# tester_tlumivek.net
KiCad netlist of a schematic drawn in EAGLE
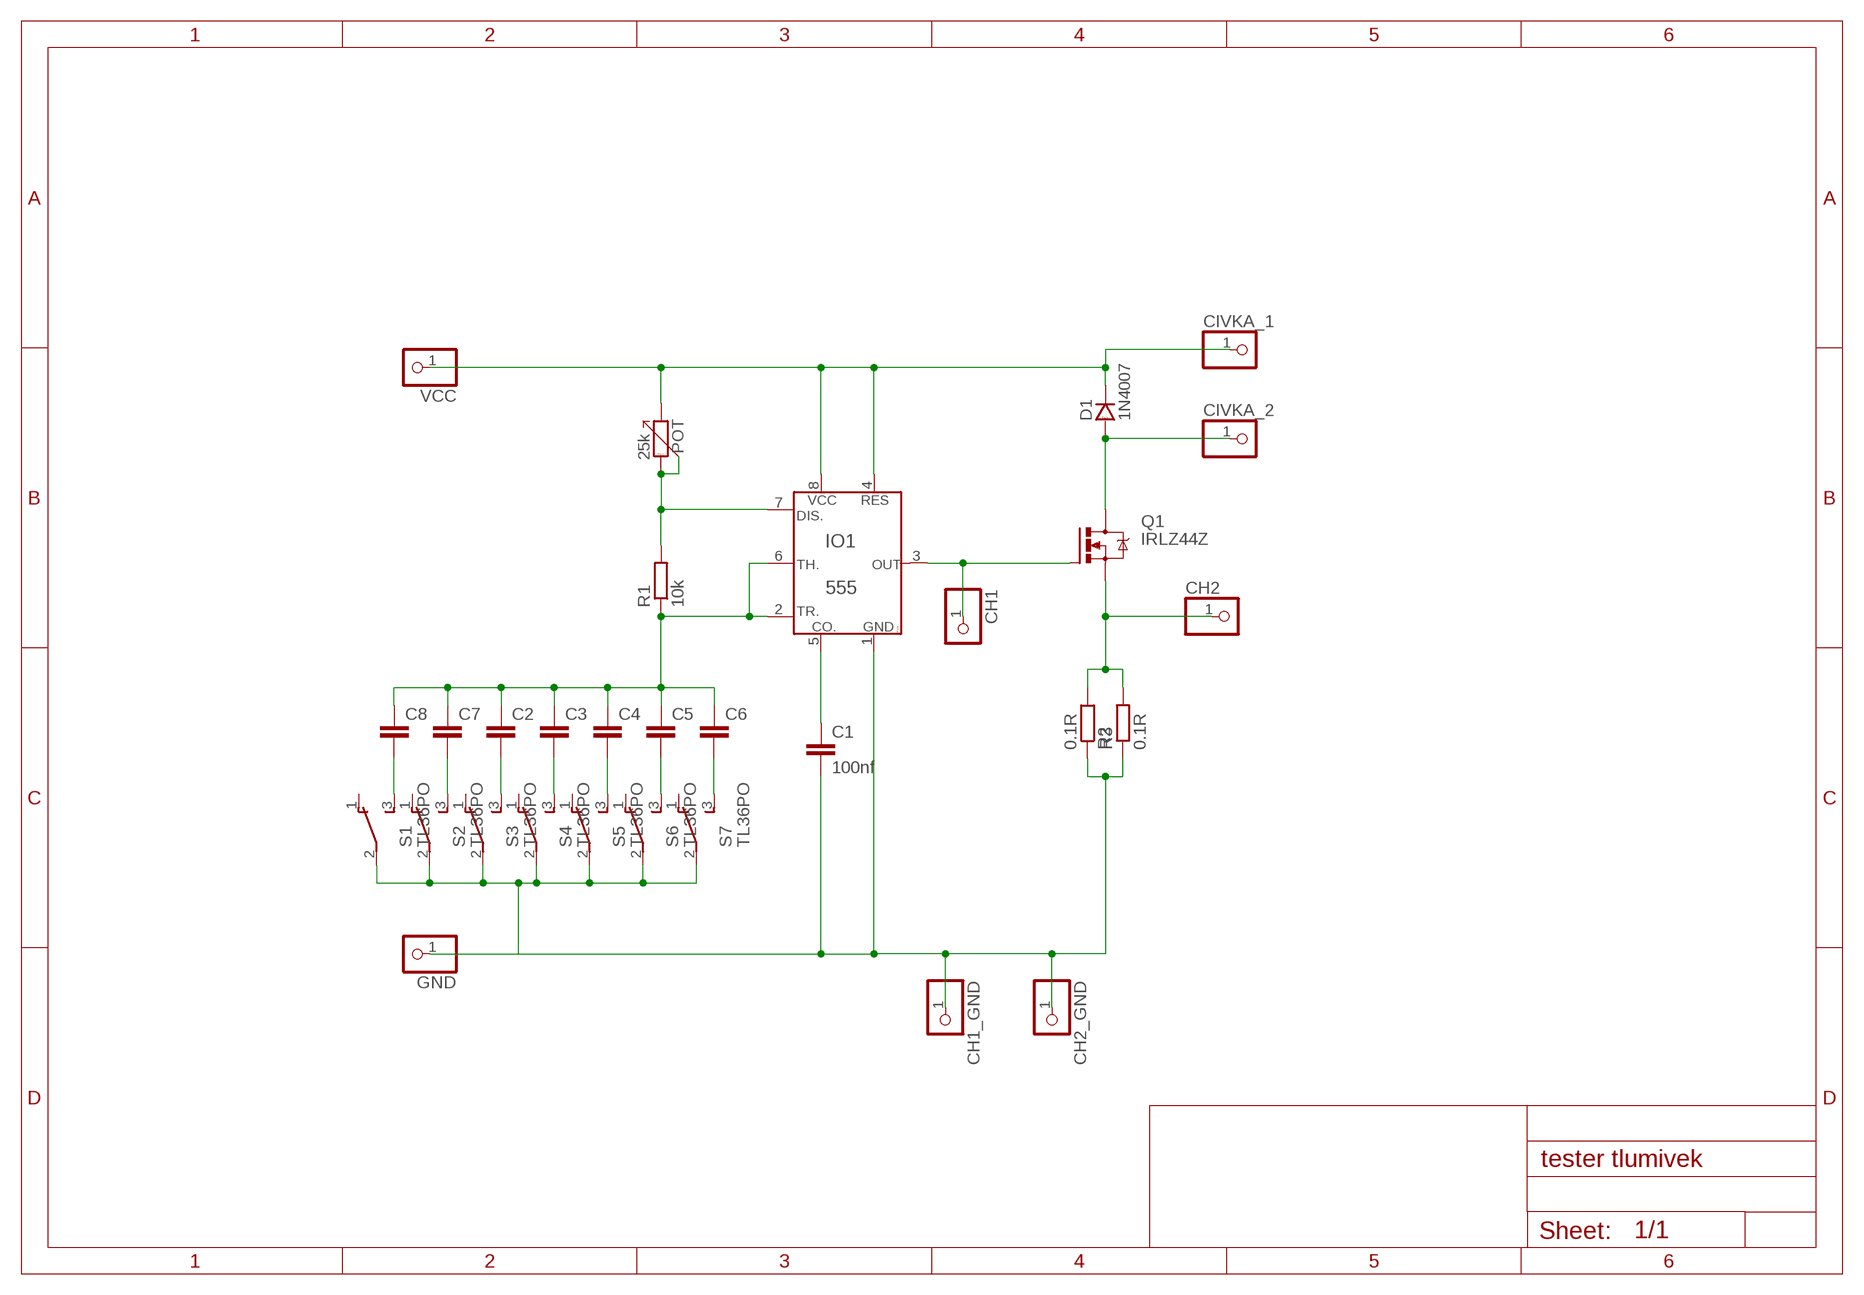
[diagram p0: schematic, sheet 1]

(export (version "E")
  (design (tool "Eeschema 10.0.6"))
  (components
    (comp (ref "C1")
      (value "100nf")
      (footprint "eagle-import:C075-042X103")
      (libsource (lib "eagle-import") (part "C-EU075-042X103"))
    )
    (comp (ref "C2")
      (value "C-EU075-042X103")
      (footprint "eagle-import:C075-042X103")
      (libsource (lib "eagle-import") (part "C-EU075-042X103"))
    )
    (comp (ref "C3")
      (value "C-EU075-042X103")
      (footprint "eagle-import:C075-042X103")
      (libsource (lib "eagle-import") (part "C-EU075-042X103"))
    )
    (comp (ref "C4")
      (value "C-EU075-042X103")
      (footprint "eagle-import:C075-042X103")
      (libsource (lib "eagle-import") (part "C-EU075-042X103"))
    )
    (comp (ref "C5")
      (value "C-EU075-042X103")
      (footprint "eagle-import:C075-042X103")
      (libsource (lib "eagle-import") (part "C-EU075-042X103"))
    )
    (comp (ref "C6")
      (value "C-EU075-042X103")
      (footprint "eagle-import:C075-042X103")
      (libsource (lib "eagle-import") (part "C-EU075-042X103"))
    )
    (comp (ref "C7")
      (value "C-EU075-042X103")
      (footprint "eagle-import:C075-042X103")
      (libsource (lib "eagle-import") (part "C-EU075-042X103"))
    )
    (comp (ref "C8")
      (value "C-EU075-042X103")
      (footprint "eagle-import:C075-042X103")
      (libsource (lib "eagle-import") (part "C-EU075-042X103"))
    )
    (comp (ref "CH1")
      (value "PINHD-1X1")
      (footprint "eagle-import:1X01")
      (libsource (lib "eagle-import") (part "PINHD-1X1"))
    )
    (comp (ref "CH1_GND")
      (value "PINHD-1X1")
      (footprint "eagle-import:1X01")
      (libsource (lib "eagle-import") (part "PINHD-1X1"))
    )
    (comp (ref "CH2")
      (value "PINHD-1X1")
      (footprint "eagle-import:1X01")
      (libsource (lib "eagle-import") (part "PINHD-1X1"))
    )
    (comp (ref "CH2_GND")
      (value "PINHD-1X1")
      (footprint "eagle-import:1X01")
      (libsource (lib "eagle-import") (part "PINHD-1X1"))
    )
    (comp (ref "CIVKA_1")
      (value "PINHD-1X1")
      (footprint "eagle-import:1X01")
      (libsource (lib "eagle-import") (part "PINHD-1X1"))
    )
    (comp (ref "CIVKA_2")
      (value "PINHD-1X1")
      (footprint "eagle-import:1X01")
      (libsource (lib "eagle-import") (part "PINHD-1X1"))
    )
    (comp (ref "D1")
      (value "1N4007")
      (footprint "eagle-import:DO41")
      (libsource (lib "eagle-import") (part "1N4007"))
    )
    (comp (ref "GND")
      (value "PINHD-1X1")
      (footprint "eagle-import:1X01")
      (libsource (lib "eagle-import") (part "PINHD-1X1"))
    )
    (comp (ref "IO1")
      (value "555")
      (footprint "eagle-import:DIL8")
      (libsource (lib "eagle-import") (part "555"))
    )
    (comp (ref "POT")
      (value "25k")
      (footprint "eagle-import:PC16ML")
      (libsource (lib "eagle-import") (part "PC16ML"))
    )
    (comp (ref "Q1")
      (value "IRLZ44Z")
      (footprint "eagle-import:TO220BH")
      (libsource (lib "eagle-import") (part "IRLZ44Z"))
    )
    (comp (ref "R1")
      (value "10k")
      (footprint "eagle-import:0207_10")
      (libsource (lib "eagle-import") (part "R-EU_0207/10"))
    )
    (comp (ref "R2")
      (value "0.1R")
      (footprint "eagle-import:0617_17")
      (libsource (lib "eagle-import") (part "R-EU_0617/17"))
    )
    (comp (ref "R3")
      (value "0.1R")
      (footprint "eagle-import:0617_17")
      (libsource (lib "eagle-import") (part "R-EU_0617/17"))
    )
    (comp (ref "S1")
      (value "TL36PO")
      (footprint "eagle-import:TL3XPO")
      (libsource (lib "eagle-import") (part "TL36PO"))
    )
    (comp (ref "S2")
      (value "TL36PO")
      (footprint "eagle-import:TL3XPO")
      (libsource (lib "eagle-import") (part "TL36PO"))
    )
    (comp (ref "S3")
      (value "TL36PO")
      (footprint "eagle-import:TL3XPO")
      (libsource (lib "eagle-import") (part "TL36PO"))
    )
    (comp (ref "S4")
      (value "TL36PO")
      (footprint "eagle-import:TL3XPO")
      (libsource (lib "eagle-import") (part "TL36PO"))
    )
    (comp (ref "S5")
      (value "TL36PO")
      (footprint "eagle-import:TL3XPO")
      (libsource (lib "eagle-import") (part "TL36PO"))
    )
    (comp (ref "S6")
      (value "TL36PO")
      (footprint "eagle-import:TL3XPO")
      (libsource (lib "eagle-import") (part "TL36PO"))
    )
    (comp (ref "S7")
      (value "TL36PO")
      (footprint "eagle-import:TL3XPO")
      (libsource (lib "eagle-import") (part "TL36PO"))
    )
    (comp (ref "VCC")
      (value "PINHD-1X1")
      (footprint "eagle-import:1X01")
      (libsource (lib "eagle-import") (part "PINHD-1X1"))
    )
  )
  (nets
    (net (code "1") (name "Net-(CH2-Pad1)") (class "Default")
      (node (ref "CH2") (pin "1") (pinfunction "1_1") (pintype "passive"))
      (node (ref "Q1") (pin "S") (pinfunction "S_S") (pintype "passive"))
      (node (ref "R2") (pin "2") (pinfunction "2_2") (pintype "passive"))
      (node (ref "R3") (pin "2") (pinfunction "2_2") (pintype "passive"))
    )
    (net (code "2") (name "Net-(CIVKA_2-Pad1)") (class "Default")
      (node (ref "CIVKA_2") (pin "1") (pinfunction "1_1") (pintype "passive"))
      (node (ref "D1") (pin "A") (pinfunction "A_A") (pintype "passive"))
      (node (ref "Q1") (pin "D") (pinfunction "D_D") (pintype "passive"))
    )
    (net (code "3") (name "Net-(IO1-CO.)") (class "Default")
      (node (ref "C1") (pin "1") (pinfunction "1_1") (pintype "passive"))
      (node (ref "IO1") (pin "5") (pinfunction "CO._5") (pintype "input"))
    )
    (net (code "4") (name "Net-(IO1-DIS.)") (class "Default")
      (node (ref "IO1") (pin "7") (pinfunction "DIS._7") (pintype "input"))
      (node (ref "POT") (pin "2") (pinfunction "2_2") (pintype "passive"))
      (node (ref "POT") (pin "3") (pinfunction "3_3") (pintype "passive"))
      (node (ref "R1") (pin "2") (pinfunction "2_2") (pintype "passive"))
    )
    (net (code "5") (name "Net-(IO1-GND)") (class "Default")
      (node (ref "C1") (pin "2") (pinfunction "2_2") (pintype "passive"))
      (node (ref "CH1_GND") (pin "1") (pinfunction "1_1") (pintype "passive"))
      (node (ref "CH2_GND") (pin "1") (pinfunction "1_1") (pintype "passive"))
      (node (ref "GND") (pin "1") (pinfunction "1_1") (pintype "passive"))
      (node (ref "IO1") (pin "1") (pinfunction "GND_1") (pintype "power_in"))
      (node (ref "R2") (pin "1") (pinfunction "1_1") (pintype "passive"))
      (node (ref "R3") (pin "1") (pinfunction "1_1") (pintype "passive"))
      (node (ref "S1") (pin "2") (pinfunction "P_2") (pintype "passive"))
      (node (ref "S2") (pin "2") (pinfunction "P_2") (pintype "passive"))
      (node (ref "S3") (pin "2") (pinfunction "P_2") (pintype "passive"))
      (node (ref "S4") (pin "2") (pinfunction "P_2") (pintype "passive"))
      (node (ref "S5") (pin "2") (pinfunction "P_2") (pintype "passive"))
      (node (ref "S6") (pin "2") (pinfunction "P_2") (pintype "passive"))
      (node (ref "S7") (pin "2") (pinfunction "P_2") (pintype "passive"))
    )
    (net (code "6") (name "Net-(IO1-OUT)") (class "Default")
      (node (ref "CH1") (pin "1") (pinfunction "1_1") (pintype "passive"))
      (node (ref "IO1") (pin "3") (pinfunction "OUT_3") (pintype "output"))
      (node (ref "Q1") (pin "G") (pinfunction "G_G") (pintype "passive"))
    )
    (net (code "7") (name "Net-(IO1-RES)") (class "Default")
      (node (ref "CIVKA_1") (pin "1") (pinfunction "1_1") (pintype "passive"))
      (node (ref "D1") (pin "K") (pinfunction "K_K") (pintype "passive"))
      (node (ref "IO1") (pin "4") (pinfunction "RES_4") (pintype "input"))
      (node (ref "IO1") (pin "8") (pinfunction "VCC_8") (pintype "power_in"))
      (node (ref "POT") (pin "1") (pinfunction "1_1") (pintype "passive"))
      (node (ref "VCC") (pin "1") (pinfunction "1_1") (pintype "passive"))
    )
    (net (code "8") (name "Net-(IO1-TH.)") (class "Default")
      (node (ref "C2") (pin "1") (pinfunction "1_1") (pintype "passive"))
      (node (ref "C3") (pin "1") (pinfunction "1_1") (pintype "passive"))
      (node (ref "C4") (pin "1") (pinfunction "1_1") (pintype "passive"))
      (node (ref "C5") (pin "1") (pinfunction "1_1") (pintype "passive"))
      (node (ref "C6") (pin "1") (pinfunction "1_1") (pintype "passive"))
      (node (ref "C7") (pin "1") (pinfunction "1_1") (pintype "passive"))
      (node (ref "C8") (pin "1") (pinfunction "1_1") (pintype "passive"))
      (node (ref "IO1") (pin "2") (pinfunction "TR._2") (pintype "input"))
      (node (ref "IO1") (pin "6") (pinfunction "TH._6") (pintype "input"))
      (node (ref "R1") (pin "1") (pinfunction "1_1") (pintype "passive"))
    )
    (net (code "9") (name "Net-(S1-S)") (class "Default")
      (node (ref "C8") (pin "2") (pinfunction "2_2") (pintype "passive"))
      (node (ref "S1") (pin "3") (pinfunction "S_3") (pintype "passive"))
    )
    (net (code "10") (name "Net-(S2-S)") (class "Default")
      (node (ref "C7") (pin "2") (pinfunction "2_2") (pintype "passive"))
      (node (ref "S2") (pin "3") (pinfunction "S_3") (pintype "passive"))
    )
    (net (code "11") (name "Net-(S3-S)") (class "Default")
      (node (ref "C2") (pin "2") (pinfunction "2_2") (pintype "passive"))
      (node (ref "S3") (pin "3") (pinfunction "S_3") (pintype "passive"))
    )
    (net (code "12") (name "Net-(S4-S)") (class "Default")
      (node (ref "C3") (pin "2") (pinfunction "2_2") (pintype "passive"))
      (node (ref "S4") (pin "3") (pinfunction "S_3") (pintype "passive"))
    )
    (net (code "13") (name "Net-(S5-S)") (class "Default")
      (node (ref "C4") (pin "2") (pinfunction "2_2") (pintype "passive"))
      (node (ref "S5") (pin "3") (pinfunction "S_3") (pintype "passive"))
    )
    (net (code "14") (name "Net-(S6-S)") (class "Default")
      (node (ref "C5") (pin "2") (pinfunction "2_2") (pintype "passive"))
      (node (ref "S6") (pin "3") (pinfunction "S_3") (pintype "passive"))
    )
    (net (code "15") (name "Net-(S7-S)") (class "Default")
      (node (ref "C6") (pin "2") (pinfunction "2_2") (pintype "passive"))
      (node (ref "S7") (pin "3") (pinfunction "S_3") (pintype "passive"))
    )
    (net (code "16") (name "unconnected-(S1-O-Pad1)") (class "Default")
      (node (ref "S1") (pin "1") (pinfunction "O_1") (pintype "passive"))
    )
    (net (code "17") (name "unconnected-(S2-O-Pad1)") (class "Default")
      (node (ref "S2") (pin "1") (pinfunction "O_1") (pintype "passive"))
    )
    (net (code "18") (name "unconnected-(S3-O-Pad1)") (class "Default")
      (node (ref "S3") (pin "1") (pinfunction "O_1") (pintype "passive"))
    )
    (net (code "19") (name "unconnected-(S4-O-Pad1)") (class "Default")
      (node (ref "S4") (pin "1") (pinfunction "O_1") (pintype "passive"))
    )
    (net (code "20") (name "unconnected-(S5-O-Pad1)") (class "Default")
      (node (ref "S5") (pin "1") (pinfunction "O_1") (pintype "passive"))
    )
    (net (code "21") (name "unconnected-(S6-O-Pad1)") (class "Default")
      (node (ref "S6") (pin "1") (pinfunction "O_1") (pintype "passive"))
    )
    (net (code "22") (name "unconnected-(S7-O-Pad1)") (class "Default")
      (node (ref "S7") (pin "1") (pinfunction "O_1") (pintype "passive"))
    )
  )
)
